# Nano_V2-2.net
KiCad netlist of a schematic drawn in EAGLE
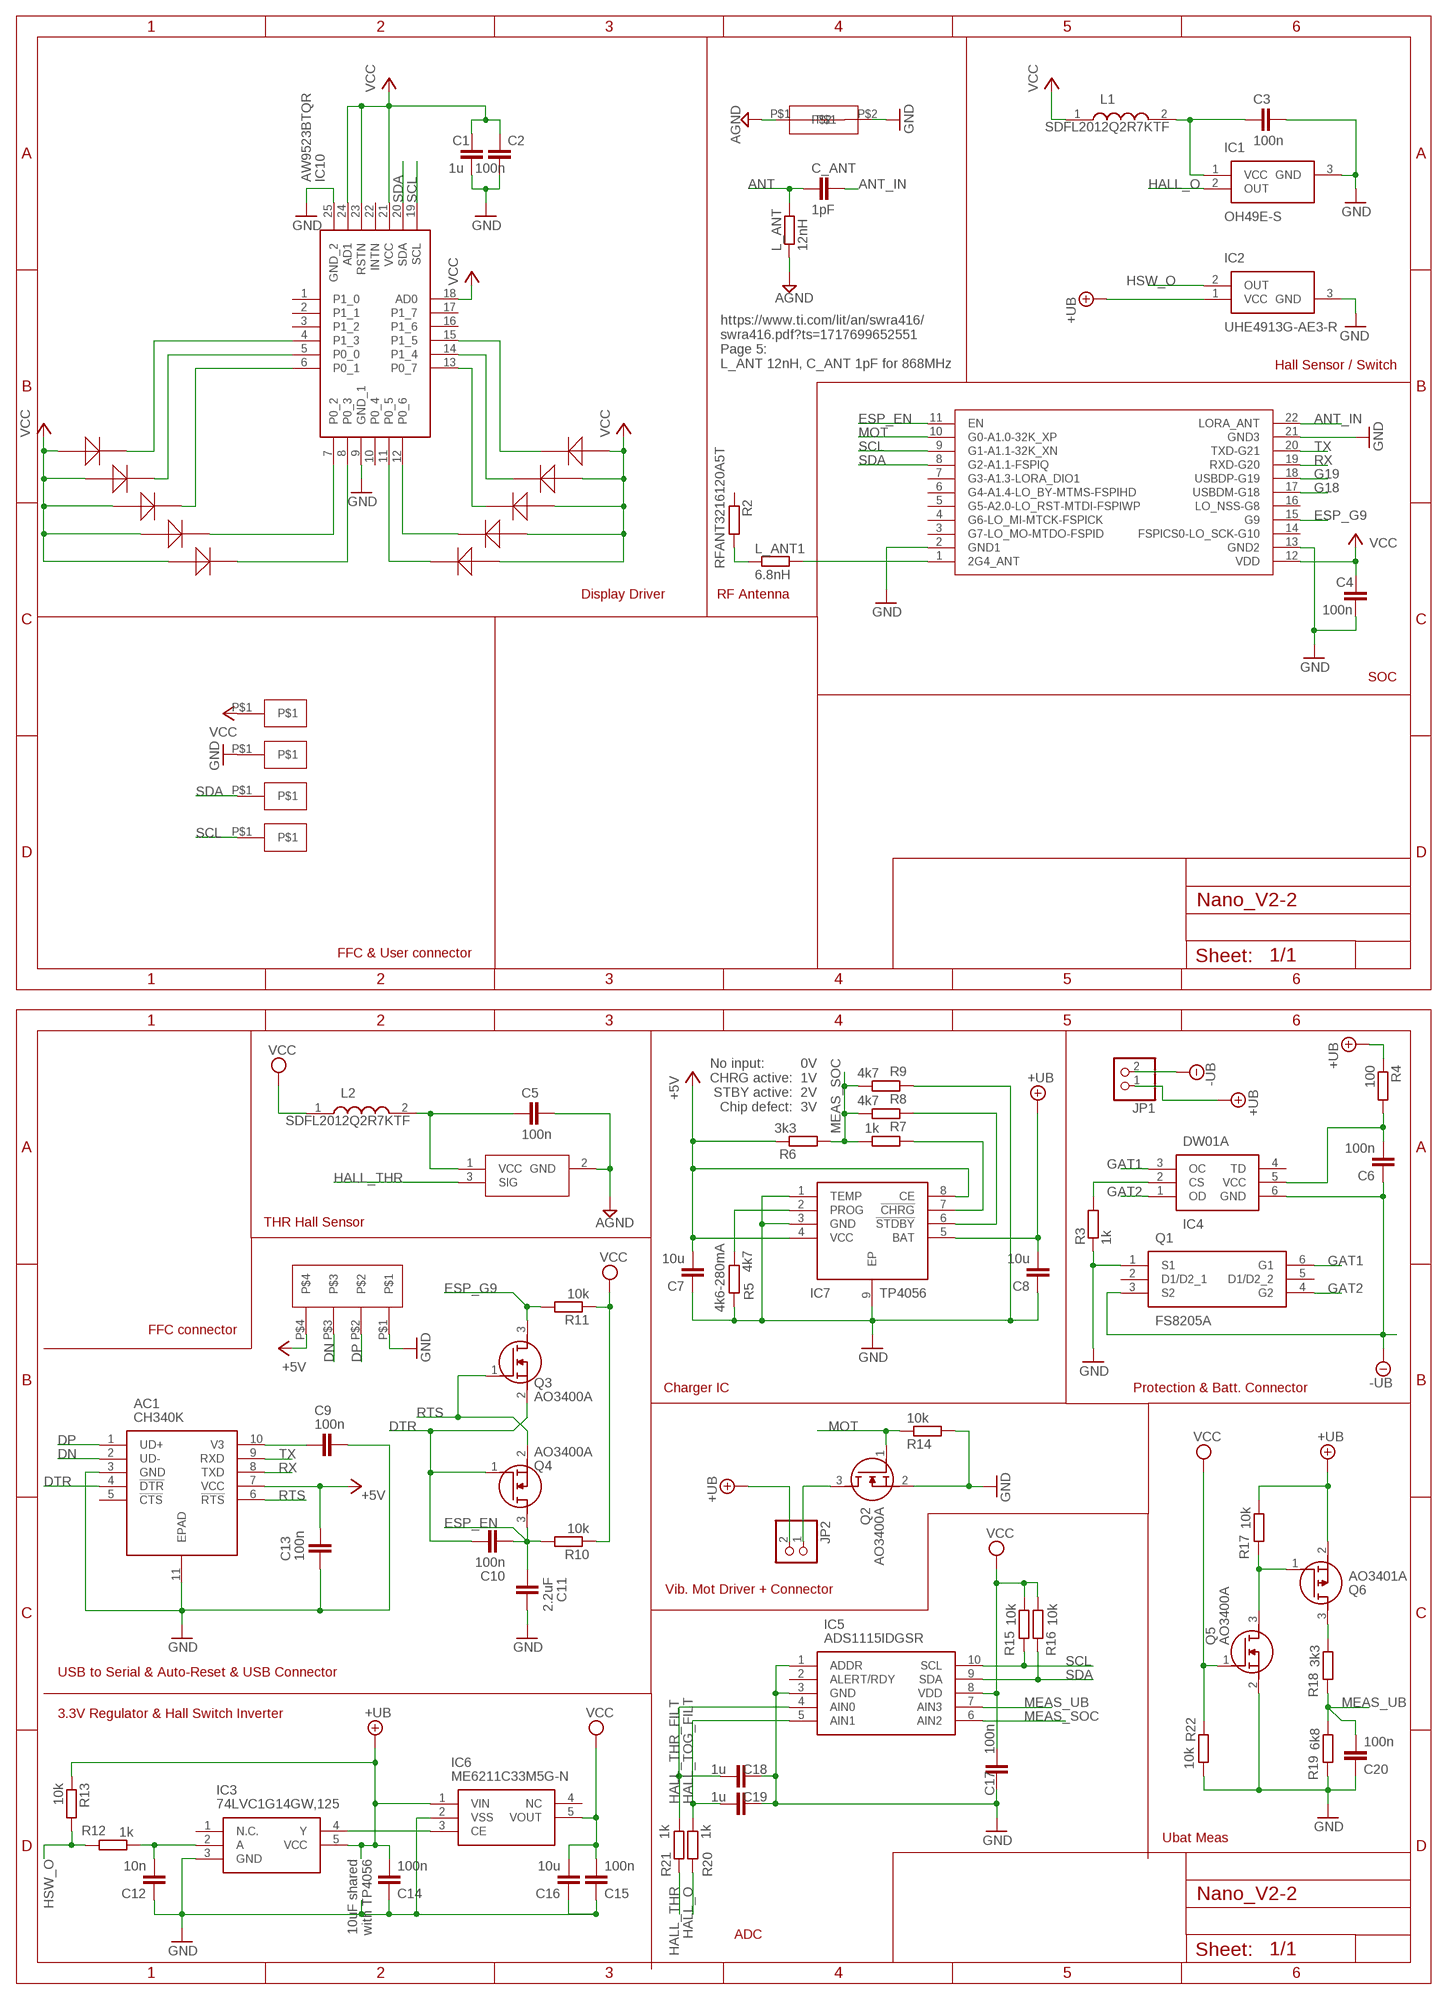
[diagram p0: schematic, sheet 1]

(export (version "E")
  (design (tool "Eeschema 10.0.6"))
  (components
    (comp (ref "AC1")
      (value "CH340K")
      (footprint "eagle-import:SOP100P600X180-11N")
      (libsource (lib "eagle-import") (part "CH340K"))
    )
    (comp (ref "C1")
      (value "1u")
      (footprint "eagle-import:C0603")
      (libsource (lib "eagle-import") (part "C-EUC0603"))
    )
    (comp (ref "C2")
      (value "100n")
      (footprint "eagle-import:C0603")
      (libsource (lib "eagle-import") (part "C-EUC0603"))
    )
    (comp (ref "C3")
      (value "100n")
      (footprint "eagle-import:C0603")
      (libsource (lib "eagle-import") (part "C-EUC0603"))
    )
    (comp (ref "C4")
      (value "100n")
      (footprint "eagle-import:C0603")
      (libsource (lib "eagle-import") (part "C-EUC0603"))
    )
    (comp (ref "C5")
      (value "100n")
      (footprint "eagle-import:C0603")
      (libsource (lib "eagle-import") (part "C-EUC0603"))
    )
    (comp (ref "C6")
      (value "100n")
      (footprint "eagle-import:C0603")
      (libsource (lib "eagle-import") (part "C-EUC0603"))
    )
    (comp (ref "C7")
      (value "10u")
      (footprint "eagle-import:C0603")
      (libsource (lib "eagle-import") (part "C-EUC0603"))
    )
    (comp (ref "C8")
      (value "10u")
      (footprint "eagle-import:C0603")
      (libsource (lib "eagle-import") (part "C-EUC0603"))
    )
    (comp (ref "C9")
      (value "100n")
      (footprint "eagle-import:C0603")
      (libsource (lib "eagle-import") (part "C-EUC0603"))
    )
    (comp (ref "C10")
      (value "100n")
      (footprint "eagle-import:C0603")
      (libsource (lib "eagle-import") (part "C-EUC0603"))
    )
    (comp (ref "C11")
      (value "2.2uF")
      (footprint "eagle-import:C0603")
      (libsource (lib "eagle-import") (part "C-EUC0603"))
    )
    (comp (ref "C12")
      (value "10n")
      (footprint "eagle-import:C0603")
      (libsource (lib "eagle-import") (part "C-EUC0603"))
    )
    (comp (ref "C13")
      (value "100n")
      (footprint "eagle-import:C0603")
      (libsource (lib "eagle-import") (part "C-EUC0603"))
    )
    (comp (ref "C14")
      (value "100n")
      (footprint "eagle-import:C0603")
      (libsource (lib "eagle-import") (part "C-EUC0603"))
    )
    (comp (ref "C15")
      (value "100n")
      (footprint "eagle-import:C0603")
      (libsource (lib "eagle-import") (part "C-EUC0603"))
    )
    (comp (ref "C16")
      (value "10u")
      (footprint "eagle-import:C0603")
      (libsource (lib "eagle-import") (part "C-EUC0603"))
    )
    (comp (ref "C17")
      (value "100n")
      (footprint "eagle-import:C0603")
      (libsource (lib "eagle-import") (part "C-EUC0603"))
    )
    (comp (ref "C18")
      (value "1u")
      (footprint "eagle-import:C0603")
      (libsource (lib "eagle-import") (part "C-EUC0603"))
    )
    (comp (ref "C19")
      (value "1u")
      (footprint "eagle-import:C0603")
      (libsource (lib "eagle-import") (part "C-EUC0603"))
    )
    (comp (ref "C20")
      (value "100n")
      (footprint "eagle-import:C0603")
      (libsource (lib "eagle-import") (part "C-EUC0603"))
    )
    (comp (ref "C_ANT")
      (value "1pF")
      (footprint "eagle-import:C0402")
      (libsource (lib "eagle-import") (part "C-EUC0402"))
    )
    (comp (ref "IC1")
      (value "OH49E-S")
      (footprint "eagle-import:SOT95P237X112-3N")
      (fields
        (field (name "ARROW_PART_NUMBER") "DRV5055A3QDBZR")
        (field (name "MOUSER_PART_NUMBER") "595-DRV5055A3QDBZR")
      )
      (libsource (lib "eagle-import") (part "DRV5055A3QDBZR"))
    )
    (comp (ref "IC2")
      (value "UHE4913G-AE3-R")
      (footprint "eagle-import:SOT95P237X112-3N")
      (fields
        (field (name "ARROW_PART_NUMBER") "DRV5055A3QDBZR")
        (field (name "MOUSER_PART_NUMBER") "595-DRV5055A3QDBZR")
      )
      (libsource (lib "eagle-import") (part "DRV5055A3QDBZR"))
    )
    (comp (ref "IC3")
      (value "74LVC1G14GW,125")
      (footprint "eagle-import:SOT65P212X110-5N")
      (fields (field (name "MOUSER_PART_NUMBER") "771-74LVC1G14GW-G"))
      (libsource (lib "eagle-import") (part "74LVC1G14GW,125"))
    )
    (comp (ref "IC4")
      (value "DW01A")
      (footprint "eagle-import:SOT95P280X135-6N")
      (fields (field (name "MANUFACTURER_PART_NUMBER") "DW01A-G"))
      (libsource (lib "eagle-import") (part "DW01A-G"))
    )
    (comp (ref "IC5")
      (value "ADS1115IDGSR")
      (footprint "eagle-import:SOP50P490X110-10N")
      (fields (field (name "MOUSER_PART_NUMBER") "595-ADS1115IDGSR"))
      (libsource (lib "eagle-import") (part "ADS1115IDGSR"))
    )
    (comp (ref "IC6")
      (value "ME6211C33M5G-N")
      (footprint "eagle-import:SOT95P282X145-5N")
      (fields (field (name "MANUFACTURER_PART_NUMBER") "ME6211C50M5G"))
      (libsource (lib "eagle-import") (part "ME6211C50M5G"))
    )
    (comp (ref "IC7")
      (value "TP4056")
      (footprint "eagle-import:SOIC127P600X175-9N")
      (fields (field (name "MANUFACTURER_PART_NUMBER") "TP4056-42-ESOP8"))
      (libsource (lib "eagle-import") (part "TP4056-42-ESOP8"))
    )
    (comp (ref "IC10")
      (value "AW9523BTQR")
      (footprint "eagle-import:QFN50P400X400X80-25N")
      (libsource (lib "eagle-import") (part "AW9523BTQR"))
    )
    (comp (ref "JP1")
      (value "PINHD-1X2")
      (footprint "eagle-import:1X02")
      (libsource (lib "eagle-import") (part "PINHD-1X2"))
    )
    (comp (ref "JP2")
      (value "PINHD-1X2")
      (footprint "eagle-import:1X02")
      (libsource (lib "eagle-import") (part "PINHD-1X2"))
    )
    (comp (ref "L1")
      (value "SDFL2012Q2R7KTF")
      (footprint "eagle-import:INDC2112X105N")
      (libsource (lib "eagle-import") (part "SDFL2012Q2R7KTF"))
    )
    (comp (ref "L2")
      (value "SDFL2012Q2R7KTF")
      (footprint "eagle-import:INDC2112X105N")
      (libsource (lib "eagle-import") (part "SDFL2012Q2R7KTF"))
    )
    (comp (ref "L_ANT")
      (value "12nH")
      (footprint "eagle-import:R0402")
      (libsource (lib "eagle-import") (part "R-EU_R0402"))
    )
    (comp (ref "L_ANT1")
      (value "6.8nH")
      (footprint "eagle-import:R0402")
      (libsource (lib "eagle-import") (part "R-EU_R0402"))
    )
    (comp (ref "Q1")
      (value "FS8205A")
      (footprint "eagle-import:SOT95P280X125-6N")
      (libsource (lib "eagle-import") (part "FS8205A"))
    )
    (comp (ref "Q2")
      (value "AO3400A")
      (footprint "eagle-import:SOT95P280X125-3N")
      (libsource (lib "eagle-import") (part "AO3400A"))
    )
    (comp (ref "Q3")
      (value "AO3400A")
      (footprint "eagle-import:SOT95P280X125-3N")
      (libsource (lib "eagle-import") (part "AO3400A"))
    )
    (comp (ref "Q4")
      (value "AO3400A")
      (footprint "eagle-import:SOT95P280X125-3N")
      (libsource (lib "eagle-import") (part "AO3400A"))
    )
    (comp (ref "Q5")
      (value "AO3400A")
      (footprint "eagle-import:SOT95P280X125-3N")
      (libsource (lib "eagle-import") (part "AO3400A"))
    )
    (comp (ref "Q6")
      (value "AO3401A")
      (footprint "eagle-import:SOT95P280X125-3N")
      (libsource (lib "eagle-import") (part "AO3401A"))
    )
    (comp (ref "R2")
      (value "RFANT3216120A5T")
      (footprint "eagle-import:R1206")
      (libsource (lib "eagle-import") (part "R-EU_R1206"))
    )
    (comp (ref "R3")
      (value "1k")
      (footprint "eagle-import:R0603")
      (libsource (lib "eagle-import") (part "R-EU_R0603"))
    )
    (comp (ref "R4")
      (value "100")
      (footprint "eagle-import:R0603")
      (libsource (lib "eagle-import") (part "R-EU_R0603"))
    )
    (comp (ref "R5")
      (value "4k7")
      (footprint "eagle-import:R0603")
      (libsource (lib "eagle-import") (part "R-EU_R0603"))
    )
    (comp (ref "R6")
      (value "3k3")
      (footprint "eagle-import:R0603")
      (libsource (lib "eagle-import") (part "R-EU_R0603"))
    )
    (comp (ref "R7")
      (value "1k")
      (footprint "eagle-import:R0603")
      (libsource (lib "eagle-import") (part "R-EU_R0603"))
    )
    (comp (ref "R8")
      (value "4k7")
      (footprint "eagle-import:R0603")
      (libsource (lib "eagle-import") (part "R-EU_R0603"))
    )
    (comp (ref "R9")
      (value "4k7")
      (footprint "eagle-import:R0603")
      (libsource (lib "eagle-import") (part "R-EU_R0603"))
    )
    (comp (ref "R10")
      (value "10k")
      (footprint "eagle-import:R0603")
      (libsource (lib "eagle-import") (part "R-EU_R0603"))
    )
    (comp (ref "R11")
      (value "10k")
      (footprint "eagle-import:R0603")
      (libsource (lib "eagle-import") (part "R-EU_R0603"))
    )
    (comp (ref "R12")
      (value "1k")
      (footprint "eagle-import:R0603")
      (libsource (lib "eagle-import") (part "R-EU_R0603"))
    )
    (comp (ref "R13")
      (value "10k")
      (footprint "eagle-import:R0603")
      (libsource (lib "eagle-import") (part "R-EU_R0603"))
    )
    (comp (ref "R14")
      (value "10k")
      (footprint "eagle-import:R0603")
      (libsource (lib "eagle-import") (part "R-EU_R0603"))
    )
    (comp (ref "R15")
      (value "10k")
      (footprint "eagle-import:R0603")
      (libsource (lib "eagle-import") (part "R-EU_R0603"))
    )
    (comp (ref "R16")
      (value "10k")
      (footprint "eagle-import:R0603")
      (libsource (lib "eagle-import") (part "R-EU_R0603"))
    )
    (comp (ref "R17")
      (value "10k")
      (footprint "eagle-import:R0603")
      (libsource (lib "eagle-import") (part "R-EU_R0603"))
    )
    (comp (ref "R18")
      (value "3k3")
      (footprint "eagle-import:R0603")
      (libsource (lib "eagle-import") (part "R-EU_R0603"))
    )
    (comp (ref "R19")
      (value "6k8")
      (footprint "eagle-import:R0603")
      (libsource (lib "eagle-import") (part "R-EU_R0603"))
    )
    (comp (ref "R20")
      (value "1k")
      (footprint "eagle-import:R0603")
      (libsource (lib "eagle-import") (part "R-EU_R0603"))
    )
    (comp (ref "R21")
      (value "1k")
      (footprint "eagle-import:R0603")
      (libsource (lib "eagle-import") (part "R-EU_R0603"))
    )
    (comp (ref "R22")
      (value "10k")
      (footprint "eagle-import:R0603")
      (libsource (lib "eagle-import") (part "R-EU_R0603"))
    )
    (comp (ref "U$1")
      (value "LED_3MM_BIG_HOLE")
      (footprint "eagle-import:3MM_BIG_HOLE")
      (libsource (lib "eagle-import") (part "LED_3MM_BIG_HOLE"))
    )
    (comp (ref "U$2")
      (value "LED_3MM_BIG_HOLE")
      (footprint "eagle-import:3MM_BIG_HOLE")
      (libsource (lib "eagle-import") (part "LED_3MM_BIG_HOLE"))
    )
    (comp (ref "U$3")
      (value "LED_3MM_BIG_HOLE")
      (footprint "eagle-import:3MM_BIG_HOLE")
      (libsource (lib "eagle-import") (part "LED_3MM_BIG_HOLE"))
    )
    (comp (ref "U$4")
      (value "LED_3MM_BIG_HOLE")
      (footprint "eagle-import:3MM_BIG_HOLE")
      (libsource (lib "eagle-import") (part "LED_3MM_BIG_HOLE"))
    )
    (comp (ref "U$5")
      (value "HT-CT62")
      (footprint "eagle-import:HT-CT62")
      (libsource (lib "eagle-import") (part "HT-CT62"))
    )
    (comp (ref "U$6")
      (value "LED_3MM_BIG_HOLE")
      (footprint "eagle-import:3MM_BIG_HOLE")
      (libsource (lib "eagle-import") (part "LED_3MM_BIG_HOLE"))
    )
    (comp (ref "U$7")
      (value "NETTIE_0.6MM")
      (footprint "eagle-import:0.6MM")
      (libsource (lib "eagle-import") (part "NETTIE_0.6MM"))
    )
    (comp (ref "U$8")
      (value "OH49")
      (footprint "eagle-import:OH49")
      (libsource (lib "eagle-import") (part "OH49"))
    )
    (comp (ref "U$9")
      (value "LED_3MM_BIG_HOLE")
      (footprint "eagle-import:3MM_BIG_HOLE")
      (libsource (lib "eagle-import") (part "LED_3MM_BIG_HOLE"))
    )
    (comp (ref "U$10")
      (value "LED_3MM_BIG_HOLE")
      (footprint "eagle-import:3MM_BIG_HOLE")
      (libsource (lib "eagle-import") (part "LED_3MM_BIG_HOLE"))
    )
    (comp (ref "U$11")
      (value "LED_3MM_BIG_HOLE")
      (footprint "eagle-import:3MM_BIG_HOLE")
      (libsource (lib "eagle-import") (part "LED_3MM_BIG_HOLE"))
    )
    (comp (ref "U$12")
      (value "1P")
      (footprint "eagle-import:1PAD")
      (libsource (lib "eagle-import") (part "1P"))
    )
    (comp (ref "U$13")
      (value "1P")
      (footprint "eagle-import:1PAD")
      (libsource (lib "eagle-import") (part "1P"))
    )
    (comp (ref "U$14")
      (value "4P")
      (footprint "eagle-import:4PAD")
      (libsource (lib "eagle-import") (part "4P"))
    )
    (comp (ref "U$15")
      (value "LED_3MM_BIG_HOLE")
      (footprint "eagle-import:3MM_BIG_HOLE")
      (libsource (lib "eagle-import") (part "LED_3MM_BIG_HOLE"))
    )
    (comp (ref "U$16")
      (value "LED_3MM_BIG_HOLE")
      (footprint "eagle-import:3MM_BIG_HOLE")
      (libsource (lib "eagle-import") (part "LED_3MM_BIG_HOLE"))
    )
    (comp (ref "U$17")
      (value "1P")
      (footprint "eagle-import:1PAD")
      (libsource (lib "eagle-import") (part "1P"))
    )
    (comp (ref "U$18")
      (value "1P")
      (footprint "eagle-import:1PAD")
      (libsource (lib "eagle-import") (part "1P"))
    )
  )
  (nets
    (net (code "1") (name "+5V") (class "Default")
      (node (ref "AC1") (pin "7") (pinfunction "VCC_7") (pintype "power_in"))
      (node (ref "C13") (pin "1") (pinfunction "1_1") (pintype "passive"))
      (node (ref "C7") (pin "2") (pinfunction "2_2") (pintype "passive"))
      (node (ref "IC7") (pin "4") (pinfunction "VCC_4") (pintype "bidirectional"))
      (node (ref "IC7") (pin "8") (pinfunction "CE_8") (pintype "bidirectional"))
      (node (ref "R6") (pin "2") (pinfunction "2_2") (pintype "passive"))
      (node (ref "U$14") (pin "P$4") (pinfunction "P$4_P$4") (pintype "bidirectional"))
    )
    (net (code "2") (name "+UB") (class "Default")
      (node (ref "C14") (pin "2") (pinfunction "2_2") (pintype "passive"))
      (node (ref "C8") (pin "2") (pinfunction "2_2") (pintype "passive"))
      (node (ref "IC2") (pin "1") (pinfunction "VCC_1") (pintype "bidirectional"))
      (node (ref "IC3") (pin "5") (pinfunction "VCC_5") (pintype "bidirectional"))
      (node (ref "IC6") (pin "1") (pinfunction "VIN_1") (pintype "bidirectional"))
      (node (ref "IC7") (pin "5") (pinfunction "BAT_5") (pintype "bidirectional"))
      (node (ref "JP1") (pin "1") (pinfunction "1_1") (pintype "passive"))
      (node (ref "JP2") (pin "2") (pinfunction "2_2") (pintype "passive"))
      (node (ref "Q6") (pin "2") (pinfunction "S_2") (pintype "bidirectional"))
      (node (ref "R13") (pin "1") (pinfunction "1_1") (pintype "passive"))
      (node (ref "R17") (pin "1") (pinfunction "1_1") (pintype "passive"))
      (node (ref "R4") (pin "1") (pinfunction "1_1") (pintype "passive"))
    )
    (net (code "3") (name "-UB") (class "Default")
      (node (ref "C6") (pin "1") (pinfunction "1_1") (pintype "passive"))
      (node (ref "IC4") (pin "6") (pinfunction "GND_6") (pintype "bidirectional"))
      (node (ref "JP1") (pin "2") (pinfunction "2_2") (pintype "passive"))
      (node (ref "Q1") (pin "3") (pinfunction "S2_3") (pintype "bidirectional"))
    )
    (net (code "4") (name "/ANT") (class "Default")
      (node (ref "C_ANT") (pin "1") (pinfunction "1_1") (pintype "passive"))
      (node (ref "L_ANT") (pin "2") (pinfunction "2_2") (pintype "passive"))
    )
    (net (code "5") (name "/ANT_IN") (class "Default")
      (node (ref "C_ANT") (pin "2") (pinfunction "2_2") (pintype "passive"))
      (node (ref "U$5") (pin "22") (pinfunction "LORA_ANT_22") (pintype "bidirectional"))
    )
    (net (code "6") (name "/DN") (class "Default")
      (node (ref "AC1") (pin "2") (pinfunction "UD-_2") (pintype "bidirectional"))
      (node (ref "U$14") (pin "P$3") (pinfunction "P$3_P$3") (pintype "bidirectional"))
    )
    (net (code "7") (name "/DP") (class "Default")
      (node (ref "AC1") (pin "1") (pinfunction "UD+_1") (pintype "bidirectional"))
      (node (ref "U$14") (pin "P$2") (pinfunction "P$2_P$2") (pintype "bidirectional"))
    )
    (net (code "8") (name "/DTR") (class "Default")
      (node (ref "AC1") (pin "4") (pinfunction "~{DTR}_4") (pintype "bidirectional"))
      (node (ref "C10") (pin "1") (pinfunction "1_1") (pintype "passive"))
      (node (ref "Q3") (pin "2") (pinfunction "S_2") (pintype "bidirectional"))
      (node (ref "Q4") (pin "1") (pinfunction "G_1") (pintype "bidirectional"))
    )
    (net (code "9") (name "/ESP_EN") (class "Default")
      (node (ref "C10") (pin "2") (pinfunction "2_2") (pintype "passive"))
      (node (ref "C11") (pin "2") (pinfunction "2_2") (pintype "passive"))
      (node (ref "Q4") (pin "3") (pinfunction "D_3") (pintype "bidirectional"))
      (node (ref "R10") (pin "2") (pinfunction "2_2") (pintype "passive"))
      (node (ref "U$5") (pin "11") (pinfunction "EN_11") (pintype "bidirectional"))
    )
    (net (code "10") (name "/ESP_G9") (class "Default")
      (node (ref "Q3") (pin "3") (pinfunction "D_3") (pintype "bidirectional"))
      (node (ref "R11") (pin "2") (pinfunction "2_2") (pintype "passive"))
      (node (ref "U$5") (pin "15") (pinfunction "G9_15") (pintype "bidirectional"))
    )
    (net (code "11") (name "/G18") (class "Default")
      (node (ref "U$5") (pin "17") (pinfunction "USBDM-G18_17") (pintype "bidirectional"))
    )
    (net (code "12") (name "/G19") (class "Default")
      (node (ref "U$5") (pin "18") (pinfunction "USBDP-G19_18") (pintype "bidirectional"))
    )
    (net (code "13") (name "/GAT1") (class "Default")
      (node (ref "IC4") (pin "3") (pinfunction "OC_3") (pintype "bidirectional"))
      (node (ref "Q1") (pin "6") (pinfunction "G1_6") (pintype "bidirectional"))
    )
    (net (code "14") (name "/GAT2") (class "Default")
      (node (ref "IC4") (pin "1") (pinfunction "OD_1") (pintype "bidirectional"))
      (node (ref "Q1") (pin "4") (pinfunction "G2_4") (pintype "bidirectional"))
    )
    (net (code "15") (name "/HALL_O") (class "Default")
      (node (ref "IC1") (pin "2") (pinfunction "OUT_2") (pintype "bidirectional"))
      (node (ref "R20") (pin "2") (pinfunction "2_2") (pintype "passive"))
    )
    (net (code "16") (name "/HALL_THR") (class "Default")
      (node (ref "R21") (pin "2") (pinfunction "2_2") (pintype "passive"))
      (node (ref "U$8") (pin "3") (pinfunction "SIG_3") (pintype "bidirectional"))
    )
    (net (code "17") (name "/HALL_THR_FILT") (class "Default")
      (node (ref "C18") (pin "1") (pinfunction "1_1") (pintype "passive"))
      (node (ref "IC5") (pin "4") (pinfunction "AIN0_4") (pintype "bidirectional"))
      (node (ref "R21") (pin "1") (pinfunction "1_1") (pintype "passive"))
    )
    (net (code "18") (name "/HALL_TOG_FILT") (class "Default")
      (node (ref "C19") (pin "1") (pinfunction "1_1") (pintype "passive"))
      (node (ref "IC5") (pin "5") (pinfunction "AIN1_5") (pintype "bidirectional"))
      (node (ref "R20") (pin "1") (pinfunction "1_1") (pintype "passive"))
    )
    (net (code "19") (name "/HSW_O") (class "Default")
      (node (ref "IC2") (pin "2") (pinfunction "OUT_2") (pintype "bidirectional"))
      (node (ref "R12") (pin "2") (pinfunction "2_2") (pintype "passive"))
      (node (ref "R13") (pin "2") (pinfunction "2_2") (pintype "passive"))
    )
    (net (code "20") (name "/MEAS_SOC") (class "Default")
      (node (ref "IC5") (pin "6") (pinfunction "AIN2_6") (pintype "bidirectional"))
      (node (ref "R6") (pin "1") (pinfunction "1_1") (pintype "passive"))
      (node (ref "R7") (pin "2") (pinfunction "2_2") (pintype "passive"))
      (node (ref "R8") (pin "2") (pinfunction "2_2") (pintype "passive"))
      (node (ref "R9") (pin "2") (pinfunction "2_2") (pintype "passive"))
    )
    (net (code "21") (name "/MEAS_UB") (class "Default")
      (node (ref "C20") (pin "2") (pinfunction "2_2") (pintype "passive"))
      (node (ref "IC5") (pin "7") (pinfunction "AIN3_7") (pintype "bidirectional"))
      (node (ref "R18") (pin "2") (pinfunction "2_2") (pintype "passive"))
      (node (ref "R19") (pin "1") (pinfunction "1_1") (pintype "passive"))
    )
    (net (code "22") (name "/MOT") (class "Default")
      (node (ref "Q2") (pin "1") (pinfunction "G_1") (pintype "bidirectional"))
      (node (ref "R14") (pin "1") (pinfunction "1_1") (pintype "passive"))
      (node (ref "U$5") (pin "10") (pinfunction "G0-A1.0-32K_XP_10") (pintype "bidirectional"))
    )
    (net (code "23") (name "/RTS") (class "Default")
      (node (ref "AC1") (pin "6") (pinfunction "~{RTS}_6") (pintype "bidirectional"))
      (node (ref "Q3") (pin "1") (pinfunction "G_1") (pintype "bidirectional"))
      (node (ref "Q4") (pin "2") (pinfunction "S_2") (pintype "bidirectional"))
    )
    (net (code "24") (name "/RX") (class "Default")
      (node (ref "AC1") (pin "8") (pinfunction "TXD_8") (pintype "bidirectional"))
      (node (ref "U$5") (pin "19") (pinfunction "RXD-G20_19") (pintype "bidirectional"))
    )
    (net (code "25") (name "/SCL") (class "Default")
      (node (ref "IC10") (pin "19") (pinfunction "SCL_19") (pintype "bidirectional"))
      (node (ref "IC5") (pin "10") (pinfunction "SCL_10") (pintype "bidirectional"))
      (node (ref "R15") (pin "2") (pinfunction "2_2") (pintype "passive"))
      (node (ref "U$18") (pin "P$1") (pinfunction "P$1_P$1") (pintype "bidirectional"))
      (node (ref "U$5") (pin "9") (pinfunction "G1-A1.1-32K_XN_9") (pintype "bidirectional"))
    )
    (net (code "26") (name "/SDA") (class "Default")
      (node (ref "IC10") (pin "20") (pinfunction "SDA_20") (pintype "bidirectional"))
      (node (ref "IC5") (pin "9") (pinfunction "SDA_9") (pintype "bidirectional"))
      (node (ref "R16") (pin "2") (pinfunction "2_2") (pintype "passive"))
      (node (ref "U$17") (pin "P$1") (pinfunction "P$1_P$1") (pintype "bidirectional"))
      (node (ref "U$5") (pin "8") (pinfunction "G2-A1.1-FSPIQ_8") (pintype "bidirectional"))
    )
    (net (code "27") (name "/TX") (class "Default")
      (node (ref "AC1") (pin "9") (pinfunction "RXD_9") (pintype "bidirectional"))
      (node (ref "U$5") (pin "20") (pinfunction "TXD-G21_20") (pintype "bidirectional"))
    )
    (net (code "28") (name "AGND") (class "Default")
      (node (ref "C5") (pin "1") (pinfunction "1_1") (pintype "passive"))
      (node (ref "L_ANT") (pin "1") (pinfunction "1_1") (pintype "passive"))
      (node (ref "U$7") (pin "P$1") (pinfunction "P$1_P$1") (pintype "bidirectional"))
      (node (ref "U$8") (pin "2") (pinfunction "GND_2") (pintype "bidirectional"))
    )
    (net (code "29") (name "GND") (class "Default")
      (node (ref "AC1") (pin "11") (pinfunction "EPAD_11") (pintype "power_in"))
      (node (ref "AC1") (pin "3") (pinfunction "GND_3") (pintype "power_in"))
      (node (ref "C1") (pin "2") (pinfunction "2_2") (pintype "passive"))
      (node (ref "C11") (pin "1") (pinfunction "1_1") (pintype "passive"))
      (node (ref "C12") (pin "1") (pinfunction "1_1") (pintype "passive"))
      (node (ref "C13") (pin "2") (pinfunction "2_2") (pintype "passive"))
      (node (ref "C14") (pin "1") (pinfunction "1_1") (pintype "passive"))
      (node (ref "C15") (pin "1") (pinfunction "1_1") (pintype "passive"))
      (node (ref "C16") (pin "1") (pinfunction "1_1") (pintype "passive"))
      (node (ref "C17") (pin "2") (pinfunction "2_2") (pintype "passive"))
      (node (ref "C18") (pin "2") (pinfunction "2_2") (pintype "passive"))
      (node (ref "C19") (pin "2") (pinfunction "2_2") (pintype "passive"))
      (node (ref "C2") (pin "2") (pinfunction "2_2") (pintype "passive"))
      (node (ref "C20") (pin "1") (pinfunction "1_1") (pintype "passive"))
      (node (ref "C3") (pin "1") (pinfunction "1_1") (pintype "passive"))
      (node (ref "C4") (pin "2") (pinfunction "2_2") (pintype "passive"))
      (node (ref "C7") (pin "1") (pinfunction "1_1") (pintype "passive"))
      (node (ref "C8") (pin "1") (pinfunction "1_1") (pintype "passive"))
      (node (ref "C9") (pin "1") (pinfunction "1_1") (pintype "passive"))
      (node (ref "IC1") (pin "3") (pinfunction "GND_3") (pintype "bidirectional"))
      (node (ref "IC10") (pin "25") (pinfunction "GND_2_25") (pintype "bidirectional"))
      (node (ref "IC10") (pin "9") (pinfunction "GND_1_9") (pintype "bidirectional"))
      (node (ref "IC2") (pin "3") (pinfunction "GND_3") (pintype "bidirectional"))
      (node (ref "IC3") (pin "3") (pinfunction "GND_3") (pintype "bidirectional"))
      (node (ref "IC5") (pin "1") (pinfunction "ADDR_1") (pintype "bidirectional"))
      (node (ref "IC5") (pin "3") (pinfunction "GND_3") (pintype "bidirectional"))
      (node (ref "IC6") (pin "2") (pinfunction "VSS_2") (pintype "bidirectional"))
      (node (ref "IC7") (pin "1") (pinfunction "TEMP_1") (pintype "bidirectional"))
      (node (ref "IC7") (pin "3") (pinfunction "GND_3") (pintype "bidirectional"))
      (node (ref "IC7") (pin "9") (pinfunction "EP_9") (pintype "bidirectional"))
      (node (ref "Q1") (pin "1") (pinfunction "S1_1") (pintype "bidirectional"))
      (node (ref "Q2") (pin "2") (pinfunction "S_2") (pintype "bidirectional"))
      (node (ref "Q5") (pin "2") (pinfunction "S_2") (pintype "bidirectional"))
      (node (ref "R14") (pin "2") (pinfunction "2_2") (pintype "passive"))
      (node (ref "R19") (pin "2") (pinfunction "2_2") (pintype "passive"))
      (node (ref "R22") (pin "1") (pinfunction "1_1") (pintype "passive"))
      (node (ref "R3") (pin "1") (pinfunction "1_1") (pintype "passive"))
      (node (ref "R5") (pin "1") (pinfunction "1_1") (pintype "passive"))
      (node (ref "R9") (pin "1") (pinfunction "1_1") (pintype "passive"))
      (node (ref "U$13") (pin "P$1") (pinfunction "P$1_P$1") (pintype "bidirectional"))
      (node (ref "U$14") (pin "P$1") (pinfunction "P$1_P$1") (pintype "bidirectional"))
      (node (ref "U$5") (pin "13") (pinfunction "GND2_13") (pintype "bidirectional"))
      (node (ref "U$5") (pin "2") (pinfunction "GND1_2") (pintype "bidirectional"))
      (node (ref "U$5") (pin "21") (pinfunction "GND3_21") (pintype "bidirectional"))
      (node (ref "U$7") (pin "P$2") (pinfunction "P$2_P$2") (pintype "bidirectional"))
    )
    (net (code "30") (name "Net-(AC1-V3)") (class "Default")
      (node (ref "AC1") (pin "10") (pinfunction "V3_10") (pintype "power_in"))
      (node (ref "C9") (pin "2") (pinfunction "2_2") (pintype "passive"))
    )
    (net (code "31") (name "Net-(IC1-VCC)") (class "Default")
      (node (ref "C3") (pin "2") (pinfunction "2_2") (pintype "passive"))
      (node (ref "IC1") (pin "1") (pinfunction "VCC_1") (pintype "bidirectional"))
      (node (ref "L1") (pin "2") (pinfunction "2_2") (pintype "bidirectional"))
    )
    (net (code "32") (name "Net-(IC3-A)") (class "Default")
      (node (ref "C12") (pin "2") (pinfunction "2_2") (pintype "passive"))
      (node (ref "IC3") (pin "2") (pinfunction "A_2") (pintype "bidirectional"))
      (node (ref "R12") (pin "1") (pinfunction "1_1") (pintype "passive"))
    )
    (net (code "33") (name "Net-(IC3-Y)") (class "Default")
      (node (ref "IC3") (pin "4") (pinfunction "Y_4") (pintype "bidirectional"))
      (node (ref "IC6") (pin "3") (pinfunction "CE_3") (pintype "bidirectional"))
    )
    (net (code "34") (name "Net-(IC4-CS)") (class "Default")
      (node (ref "IC4") (pin "2") (pinfunction "CS_2") (pintype "bidirectional"))
      (node (ref "R3") (pin "2") (pinfunction "2_2") (pintype "passive"))
    )
    (net (code "35") (name "Net-(IC4-VCC)") (class "Default")
      (node (ref "C6") (pin "2") (pinfunction "2_2") (pintype "passive"))
      (node (ref "IC4") (pin "5") (pinfunction "VCC_5") (pintype "bidirectional"))
      (node (ref "R4") (pin "2") (pinfunction "2_2") (pintype "passive"))
    )
    (net (code "36") (name "Net-(IC7-PROG)") (class "Default")
      (node (ref "IC7") (pin "2") (pinfunction "PROG_2") (pintype "bidirectional"))
      (node (ref "R5") (pin "2") (pinfunction "2_2") (pintype "passive"))
    )
    (net (code "37") (name "Net-(IC7-~{CHRG})") (class "Default")
      (node (ref "IC7") (pin "7") (pinfunction "~{CHRG}_7") (pintype "bidirectional"))
      (node (ref "R7") (pin "1") (pinfunction "1_1") (pintype "passive"))
    )
    (net (code "38") (name "Net-(IC7-~{STDBY})") (class "Default")
      (node (ref "IC7") (pin "6") (pinfunction "~{STDBY}_6") (pintype "bidirectional"))
      (node (ref "R8") (pin "1") (pinfunction "1_1") (pintype "passive"))
    )
    (net (code "39") (name "Net-(IC10-P0_0)") (class "Default")
      (node (ref "IC10") (pin "5") (pinfunction "P0_0_5") (pintype "bidirectional"))
      (node (ref "U$15") (pin "P$2") (pinfunction "K_P$2") (pintype "bidirectional"))
    )
    (net (code "40") (name "Net-(IC10-P0_1)") (class "Default")
      (node (ref "IC10") (pin "6") (pinfunction "P0_1_6") (pintype "bidirectional"))
      (node (ref "U$11") (pin "P$2") (pinfunction "K_P$2") (pintype "bidirectional"))
    )
    (net (code "41") (name "Net-(IC10-P0_2)") (class "Default")
      (node (ref "IC10") (pin "7") (pinfunction "P0_2_7") (pintype "bidirectional"))
      (node (ref "U$10") (pin "P$2") (pinfunction "K_P$2") (pintype "bidirectional"))
    )
    (net (code "42") (name "Net-(IC10-P0_3)") (class "Default")
      (node (ref "IC10") (pin "8") (pinfunction "P0_3_8") (pintype "bidirectional"))
      (node (ref "U$9") (pin "P$2") (pinfunction "K_P$2") (pintype "bidirectional"))
    )
    (net (code "43") (name "Net-(IC10-P0_5)") (class "Default")
      (node (ref "IC10") (pin "11") (pinfunction "P0_5_11") (pintype "bidirectional"))
      (node (ref "U$1") (pin "P$2") (pinfunction "K_P$2") (pintype "bidirectional"))
    )
    (net (code "44") (name "Net-(IC10-P0_6)") (class "Default")
      (node (ref "IC10") (pin "12") (pinfunction "P0_6_12") (pintype "bidirectional"))
      (node (ref "U$2") (pin "P$2") (pinfunction "K_P$2") (pintype "bidirectional"))
    )
    (net (code "45") (name "Net-(IC10-P0_7)") (class "Default")
      (node (ref "IC10") (pin "13") (pinfunction "P0_7_13") (pintype "bidirectional"))
      (node (ref "U$4") (pin "P$2") (pinfunction "K_P$2") (pintype "bidirectional"))
    )
    (net (code "46") (name "Net-(IC10-P1_3)") (class "Default")
      (node (ref "IC10") (pin "4") (pinfunction "P1_3_4") (pintype "bidirectional"))
      (node (ref "U$16") (pin "P$2") (pinfunction "K_P$2") (pintype "bidirectional"))
    )
    (net (code "47") (name "Net-(IC10-P1_4)") (class "Default")
      (node (ref "IC10") (pin "14") (pinfunction "P1_4_14") (pintype "bidirectional"))
      (node (ref "U$6") (pin "P$2") (pinfunction "K_P$2") (pintype "bidirectional"))
    )
    (net (code "48") (name "Net-(IC10-P1_5)") (class "Default")
      (node (ref "IC10") (pin "15") (pinfunction "P1_5_15") (pintype "bidirectional"))
      (node (ref "U$3") (pin "P$2") (pinfunction "K_P$2") (pintype "bidirectional"))
    )
    (net (code "49") (name "Net-(L_ANT1-Pad2)") (class "Default")
      (node (ref "L_ANT1") (pin "2") (pinfunction "2_2") (pintype "passive"))
      (node (ref "R2") (pin "2") (pinfunction "2_2") (pintype "passive"))
    )
    (net (code "50") (name "Net-(Q2-D)") (class "Default")
      (node (ref "JP2") (pin "1") (pinfunction "1_1") (pintype "passive"))
      (node (ref "Q2") (pin "3") (pinfunction "D_3") (pintype "bidirectional"))
    )
    (net (code "51") (name "Net-(Q5-D)") (class "Default")
      (node (ref "Q5") (pin "3") (pinfunction "D_3") (pintype "bidirectional"))
      (node (ref "Q6") (pin "1") (pinfunction "G_1") (pintype "bidirectional"))
      (node (ref "R17") (pin "2") (pinfunction "2_2") (pintype "passive"))
    )
    (net (code "52") (name "Net-(Q6-D)") (class "Default")
      (node (ref "Q6") (pin "3") (pinfunction "D_3") (pintype "bidirectional"))
      (node (ref "R18") (pin "1") (pinfunction "1_1") (pintype "passive"))
    )
    (net (code "53") (name "Net-(U$5-2G4_ANT)") (class "Default")
      (node (ref "L_ANT1") (pin "1") (pinfunction "1_1") (pintype "passive"))
      (node (ref "U$5") (pin "1") (pinfunction "2G4_ANT_1") (pintype "bidirectional"))
    )
    (net (code "54") (name "Net-(U$8-VCC)") (class "Default")
      (node (ref "C5") (pin "2") (pinfunction "2_2") (pintype "passive"))
      (node (ref "L2") (pin "2") (pinfunction "2_2") (pintype "bidirectional"))
      (node (ref "U$8") (pin "1") (pinfunction "VCC_1") (pintype "bidirectional"))
    )
    (net (code "55") (name "VCC") (class "Default")
      (node (ref "C1") (pin "1") (pinfunction "1_1") (pintype "passive"))
      (node (ref "C15") (pin "2") (pinfunction "2_2") (pintype "passive"))
      (node (ref "C16") (pin "2") (pinfunction "2_2") (pintype "passive"))
      (node (ref "C17") (pin "1") (pinfunction "1_1") (pintype "passive"))
      (node (ref "C2") (pin "1") (pinfunction "1_1") (pintype "passive"))
      (node (ref "C4") (pin "1") (pinfunction "1_1") (pintype "passive"))
      (node (ref "IC10") (pin "18") (pinfunction "AD0_18") (pintype "bidirectional"))
      (node (ref "IC10") (pin "21") (pinfunction "VCC_21") (pintype "bidirectional"))
      (node (ref "IC10") (pin "23") (pinfunction "RSTN_23") (pintype "bidirectional"))
      (node (ref "IC10") (pin "24") (pinfunction "AD1_24") (pintype "bidirectional"))
      (node (ref "IC5") (pin "8") (pinfunction "VDD_8") (pintype "bidirectional"))
      (node (ref "IC6") (pin "5") (pinfunction "VOUT_5") (pintype "bidirectional"))
      (node (ref "L1") (pin "1") (pinfunction "1_1") (pintype "bidirectional"))
      (node (ref "L2") (pin "1") (pinfunction "1_1") (pintype "bidirectional"))
      (node (ref "Q5") (pin "1") (pinfunction "G_1") (pintype "bidirectional"))
      (node (ref "R10") (pin "1") (pinfunction "1_1") (pintype "passive"))
      (node (ref "R11") (pin "1") (pinfunction "1_1") (pintype "passive"))
      (node (ref "R15") (pin "1") (pinfunction "1_1") (pintype "passive"))
      (node (ref "R16") (pin "1") (pinfunction "1_1") (pintype "passive"))
      (node (ref "R22") (pin "2") (pinfunction "2_2") (pintype "passive"))
      (node (ref "U$1") (pin "P$1") (pinfunction "A_P$1") (pintype "bidirectional"))
      (node (ref "U$10") (pin "P$1") (pinfunction "A_P$1") (pintype "bidirectional"))
      (node (ref "U$11") (pin "P$1") (pinfunction "A_P$1") (pintype "bidirectional"))
      (node (ref "U$12") (pin "P$1") (pinfunction "P$1_P$1") (pintype "bidirectional"))
      (node (ref "U$15") (pin "P$1") (pinfunction "A_P$1") (pintype "bidirectional"))
      (node (ref "U$16") (pin "P$1") (pinfunction "A_P$1") (pintype "bidirectional"))
      (node (ref "U$2") (pin "P$1") (pinfunction "A_P$1") (pintype "bidirectional"))
      (node (ref "U$3") (pin "P$1") (pinfunction "A_P$1") (pintype "bidirectional"))
      (node (ref "U$4") (pin "P$1") (pinfunction "A_P$1") (pintype "bidirectional"))
      (node (ref "U$5") (pin "12") (pinfunction "VDD_12") (pintype "bidirectional"))
      (node (ref "U$6") (pin "P$1") (pinfunction "A_P$1") (pintype "bidirectional"))
      (node (ref "U$9") (pin "P$1") (pinfunction "A_P$1") (pintype "bidirectional"))
    )
    (net (code "56") (name "unconnected-(AC1-~{CTS}-Pad5)") (class "Default")
      (node (ref "AC1") (pin "5") (pinfunction "~{CTS}_5") (pintype "bidirectional"))
    )
    (net (code "57") (name "unconnected-(IC3-N.C.-Pad1)") (class "Default")
      (node (ref "IC3") (pin "1") (pinfunction "N.C._1") (pintype "bidirectional"))
    )
    (net (code "58") (name "unconnected-(IC4-TD-Pad4)") (class "Default")
      (node (ref "IC4") (pin "4") (pinfunction "TD_4") (pintype "bidirectional"))
    )
    (net (code "59") (name "unconnected-(IC5-ALERT{slash}RDY-Pad2)") (class "Default")
      (node (ref "IC5") (pin "2") (pinfunction "ALERT/RDY_2") (pintype "bidirectional"))
    )
    (net (code "60") (name "unconnected-(IC6-NC-Pad4)") (class "Default")
      (node (ref "IC6") (pin "4") (pinfunction "NC_4") (pintype "no_connect"))
    )
    (net (code "61") (name "unconnected-(IC10-INTN-Pad22)") (class "Default")
      (node (ref "IC10") (pin "22") (pinfunction "INTN_22") (pintype "bidirectional"))
    )
    (net (code "62") (name "unconnected-(IC10-P0_4-Pad10)") (class "Default")
      (node (ref "IC10") (pin "10") (pinfunction "P0_4_10") (pintype "bidirectional"))
    )
    (net (code "63") (name "unconnected-(IC10-P1_0-Pad1)") (class "Default")
      (node (ref "IC10") (pin "1") (pinfunction "P1_0_1") (pintype "bidirectional"))
    )
    (net (code "64") (name "unconnected-(IC10-P1_1-Pad2)") (class "Default")
      (node (ref "IC10") (pin "2") (pinfunction "P1_1_2") (pintype "bidirectional"))
    )
    (net (code "65") (name "unconnected-(IC10-P1_2-Pad3)") (class "Default")
      (node (ref "IC10") (pin "3") (pinfunction "P1_2_3") (pintype "bidirectional"))
    )
    (net (code "66") (name "unconnected-(IC10-P1_6-Pad16)") (class "Default")
      (node (ref "IC10") (pin "16") (pinfunction "P1_6_16") (pintype "bidirectional"))
    )
    (net (code "67") (name "unconnected-(IC10-P1_7-Pad17)") (class "Default")
      (node (ref "IC10") (pin "17") (pinfunction "P1_7_17") (pintype "bidirectional"))
    )
    (net (code "68") (name "unconnected-(Q1-D1{slash}D2_1-Pad2)") (class "Default")
      (node (ref "Q1") (pin "2") (pinfunction "D1/D2_1_2") (pintype "bidirectional"))
    )
    (net (code "69") (name "unconnected-(Q1-D1{slash}D2_2-Pad5)") (class "Default")
      (node (ref "Q1") (pin "5") (pinfunction "D1/D2_2_5") (pintype "bidirectional"))
    )
    (net (code "70") (name "unconnected-(R2-Pad1)") (class "Default")
      (node (ref "R2") (pin "1") (pinfunction "1_1") (pintype "passive"))
    )
    (net (code "71") (name "unconnected-(U$5-FSPICS0-LO_SCK-G10-Pad14)") (class "Default")
      (node (ref "U$5") (pin "14") (pinfunction "FSPICS0-LO_SCK-G10_14") (pintype "bidirectional"))
    )
    (net (code "72") (name "unconnected-(U$5-G3-A1.3-LORA_DIO1-Pad7)") (class "Default")
      (node (ref "U$5") (pin "7") (pinfunction "G3-A1.3-LORA_DIO1_7") (pintype "bidirectional"))
    )
    (net (code "73") (name "unconnected-(U$5-G4-A1.4-LO_BY-MTMS-FSPIHD-Pad6)") (class "Default")
      (node (ref "U$5") (pin "6") (pinfunction "G4-A1.4-LO_BY-MTMS-FSPIHD_6") (pintype "bidirectional"))
    )
    (net (code "74") (name "unconnected-(U$5-G5-A2.0-LO_RST-MTDI-FSPIWP-Pad5)") (class "Default")
      (node (ref "U$5") (pin "5") (pinfunction "G5-A2.0-LO_RST-MTDI-FSPIWP_5") (pintype "bidirectional"))
    )
    (net (code "75") (name "unconnected-(U$5-G6-LO_MI-MTCK-FSPICK-Pad4)") (class "Default")
      (node (ref "U$5") (pin "4") (pinfunction "G6-LO_MI-MTCK-FSPICK_4") (pintype "bidirectional"))
    )
    (net (code "76") (name "unconnected-(U$5-G7-LO_MO-MTDO-FSPID-Pad3)") (class "Default")
      (node (ref "U$5") (pin "3") (pinfunction "G7-LO_MO-MTDO-FSPID_3") (pintype "bidirectional"))
    )
    (net (code "77") (name "unconnected-(U$5-LO_NSS-G8-Pad16)") (class "Default")
      (node (ref "U$5") (pin "16") (pinfunction "LO_NSS-G8_16") (pintype "bidirectional"))
    )
  )
)
